# PSU_2V5_LDK130.net
KiCad netlist of a schematic drawn in Altium Designer
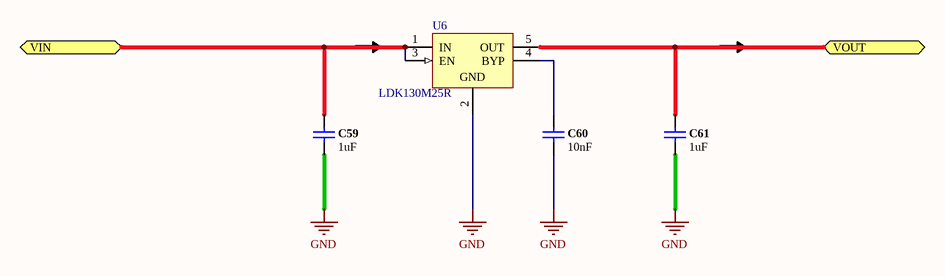
[diagram p0: PSU_2V5_LDK130.SchDoc]

(export (version "E")
  (design (tool "Eeschema 10.0.6"))
  (components
    (comp (ref "C59")
      (value "1uF")
      (footprint "0805C-GENERIC")
      (description "Capacitor, Ceramic, 10% 10V 0805 X7R")
      (fields (field (name "CAPACITANCE") "1uF") (field (name "TOLERANCE") "10 %"))
      (libsource (lib "altium-import") (part "root_0_CAP-NP_"))
    )
    (comp (ref "C60")
      (value "10nF")
      (footprint "0805C-GENERIC")
      (description "Capacitor, Ceramic, 10% 10V 0805 X7R")
      (fields (field (name "CAPACITANCE") "10nF") (field (name "TOLERANCE") "10 %"))
      (libsource (lib "altium-import") (part "root_0_CAP-NP_"))
    )
    (comp (ref "C61")
      (value "1uF")
      (footprint "0805C-GENERIC")
      (description "Capacitor, Ceramic, 10% 10V 0805 X7R")
      (fields (field (name "CAPACITANCE") "1uF") (field (name "TOLERANCE") "10 %"))
      (libsource (lib "altium-import") (part "root_0_CAP-NP_"))
    )
    (comp (ref "U6")
      (value "LDK130M25R")
      (footprint "SOT23-5L_N")
      (libsource (lib "STMicroelectronics Power Management Linear Regulator") (part "LD2985BM25R"))
    )
  )
  (nets
    (net (code "1") (name "/VIN") (class "Default")
      (node (ref "C59") (pin "1") (pinfunction "1_1") (pintype "passive"))
      (node (ref "U6") (pin "1") (pinfunction "IN_1") (pintype "power_in"))
      (node (ref "U6") (pin "3") (pinfunction "EN_3") (pintype "input"))
    )
    (net (code "2") (name "/VOUT") (class "Default")
      (node (ref "C61") (pin "1") (pinfunction "1_1") (pintype "passive"))
      (node (ref "U6") (pin "5") (pinfunction "OUT_5") (pintype "power_in"))
    )
    (net (code "3") (name "GND") (class "Default")
      (node (ref "C59") (pin "2") (pinfunction "2_2") (pintype "passive"))
      (node (ref "C60") (pin "2") (pinfunction "2_2") (pintype "passive"))
      (node (ref "C61") (pin "2") (pinfunction "2_2") (pintype "passive"))
      (node (ref "U6") (pin "2") (pinfunction "GND_2") (pintype "power_in"))
    )
    (net (code "4") (name "Net-(U6-BYP)") (class "Default")
      (node (ref "C60") (pin "1") (pinfunction "1_1") (pintype "passive"))
      (node (ref "U6") (pin "4") (pinfunction "BYP_4") (pintype "passive"))
    )
  )
)
